# SCH_555-Circuit_2025-03-12.net
KiCad netlist of a schematic drawn in EasyEDA
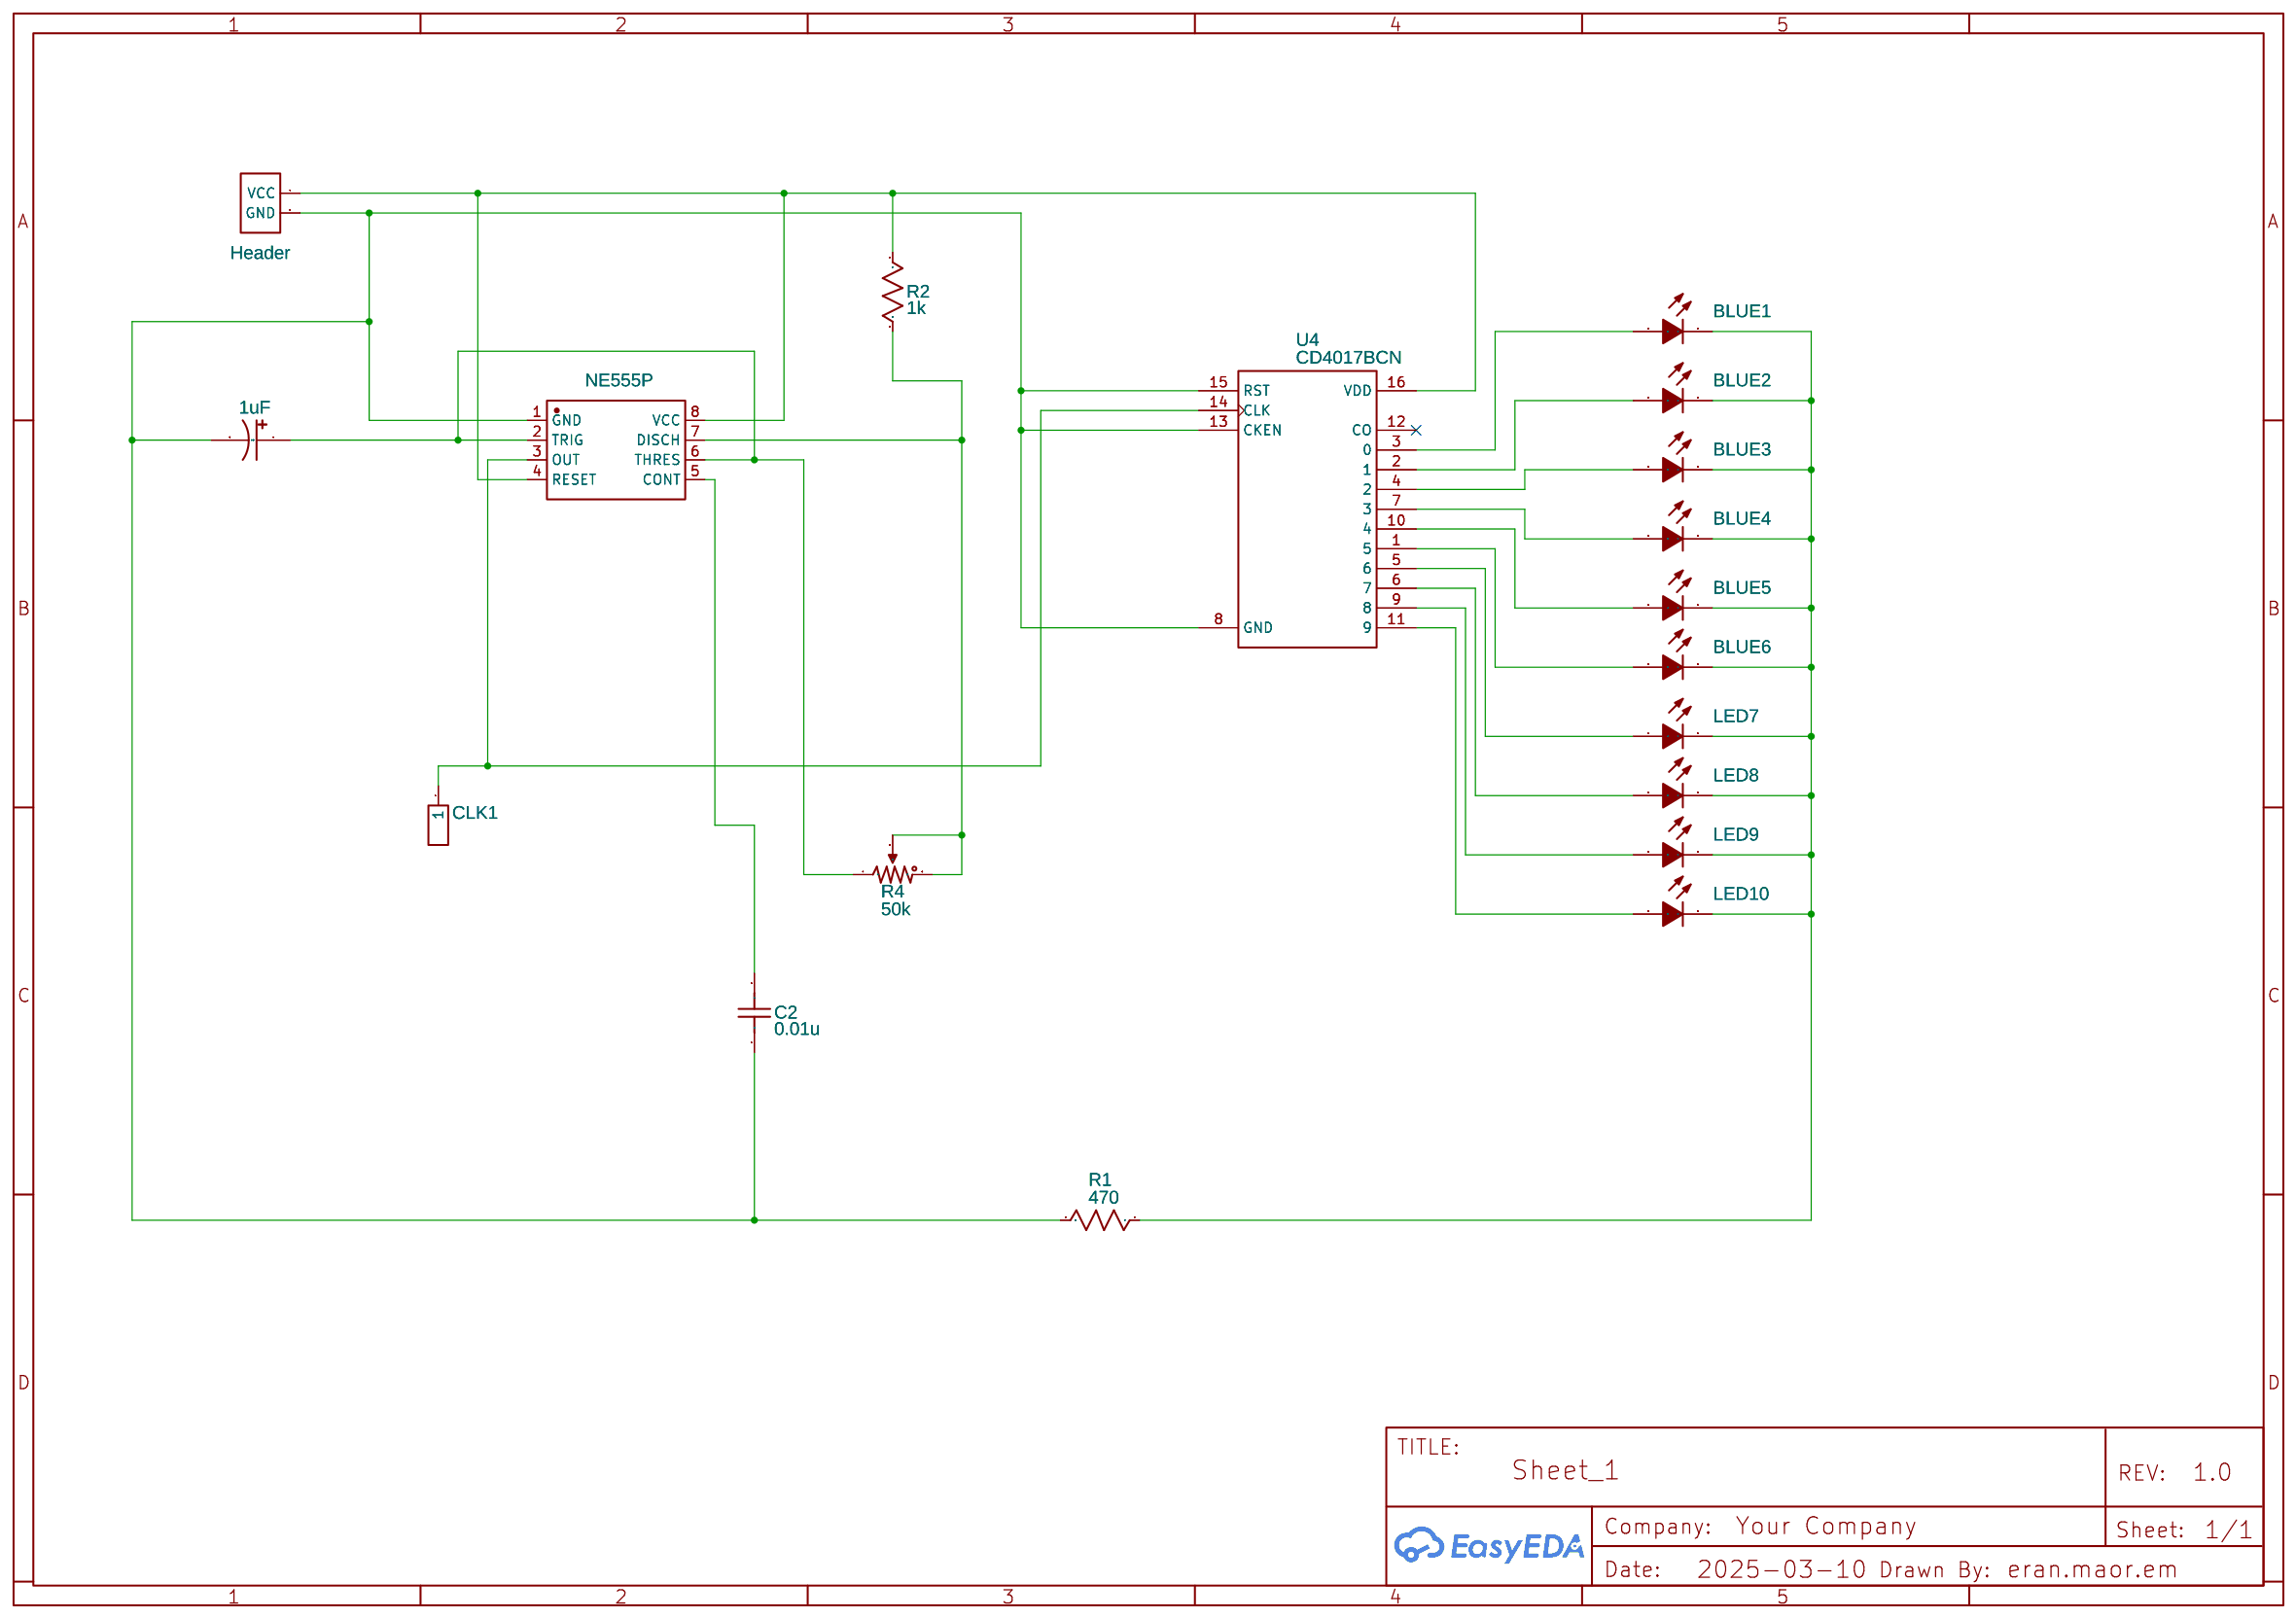
[diagram p0: schematic sheet]

(export (version "E")
  (design (tool "Eeschema 10.0.6"))
  (components
    (comp (ref "BLUE1") (value "LED_5MM") (libsource (lib "") (part "LED_5MM_1")))
    (comp (ref "BLUE2") (value "LED_5MM") (libsource (lib "") (part "LED_5MM_1")))
    (comp (ref "BLUE3") (value "LED_5MM") (libsource (lib "") (part "LED_5MM_1")))
    (comp (ref "BLUE4") (value "LED_5MM") (libsource (lib "") (part "LED_5MM_1")))
    (comp (ref "BLUE5") (value "LED_5MM") (libsource (lib "") (part "LED_5MM_1")))
    (comp (ref "BLUE6") (value "LED_5MM") (libsource (lib "") (part "LED_5MM_1")))
    (comp (ref "C1")
      (value "1uF")
      (fields (field (name "Manufacturer Part") "UVZ1H010MDD") (field (name "Manufacturer") "Nichicon(尼吉康)"))
      (libsource (lib "") (part "UVZ1H010MDD"))
    )
    (comp (ref "C2") (value "0.01u") (libsource (lib "") (part "C_0603_US")))
    (comp (ref "CLK1")
      (value "C81276")
      (fields
        (field (name "Manufacturer Part") "2.54-1*1P针")
        (field (name "Manufacturer") "BOOMELE(Boom Precision Elec)")
      )
      (libsource (lib "") (part "Header-Male-2.54_1x1"))
    )
    (comp (ref "H1") (value "Header") (libsource (lib "") (part "HEADER-FEMALE-2.54_1X2")))
    (comp (ref "LED7") (value "LED_5MM") (libsource (lib "") (part "LED_5MM")))
    (comp (ref "LED8") (value "LED_5MM") (libsource (lib "") (part "LED_5MM")))
    (comp (ref "LED9") (value "LED_5MM") (libsource (lib "") (part "LED_5MM")))
    (comp (ref "LED10") (value "LED_5MM") (libsource (lib "") (part "LED_5MM")))
    (comp (ref "R1")
      (value "470")
      (fields (field (name "Manufacturer Part") "?"))
      (libsource (lib "") (part "Resistor"))
    )
    (comp (ref "R2")
      (value "1k")
      (fields (field (name "Manufacturer Part") "?"))
      (libsource (lib "") (part "Resistor_1"))
    )
    (comp (ref "R4")
      (value "50k")
      (fields (field (name "Manufacturer Part") "?"))
      (libsource (lib "") (part "Potentiometer"))
    )
    (comp (ref "U2")
      (value "NE555P")
      (fields (field (name "Manufacturer") "TI(德州仪器)"))
      (libsource (lib "") (part "NE555P"))
    )
    (comp (ref "U4") (value "CD4017BCN") (libsource (lib "") (part "CD4017BCN")))
  )
  (nets
    (net (code "1") (name "Net-(BLUE1-A)") (class "Default")
      (node (ref "BLUE1") (pin "1") (pinfunction "A_1") (pintype "input"))
      (node (ref "U4") (pin "3") (pinfunction "0_3") (pintype "output"))
    )
    (net (code "2") (name "Net-(BLUE1-K)") (class "Default")
      (node (ref "BLUE1") (pin "2") (pinfunction "K_2") (pintype "input"))
      (node (ref "BLUE2") (pin "2") (pinfunction "K_2") (pintype "input"))
      (node (ref "BLUE3") (pin "2") (pinfunction "K_2") (pintype "input"))
      (node (ref "BLUE4") (pin "2") (pinfunction "K_2") (pintype "input"))
      (node (ref "BLUE5") (pin "2") (pinfunction "K_2") (pintype "input"))
      (node (ref "BLUE6") (pin "2") (pinfunction "K_2") (pintype "input"))
      (node (ref "LED10") (pin "2") (pinfunction "K_2") (pintype "input"))
      (node (ref "LED7") (pin "2") (pinfunction "K_2") (pintype "input"))
      (node (ref "LED8") (pin "2") (pinfunction "K_2") (pintype "input"))
      (node (ref "LED9") (pin "2") (pinfunction "K_2") (pintype "input"))
      (node (ref "R1") (pin "1") (pinfunction "1_1") (pintype "unspecified"))
    )
    (net (code "3") (name "Net-(BLUE2-A)") (class "Default")
      (node (ref "BLUE2") (pin "1") (pinfunction "A_1") (pintype "input"))
      (node (ref "U4") (pin "2") (pinfunction "1_2") (pintype "output"))
    )
    (net (code "4") (name "Net-(BLUE3-A)") (class "Default")
      (node (ref "BLUE3") (pin "1") (pinfunction "A_1") (pintype "input"))
      (node (ref "U4") (pin "4") (pinfunction "2_4") (pintype "output"))
    )
    (net (code "5") (name "Net-(BLUE4-A)") (class "Default")
      (node (ref "BLUE4") (pin "1") (pinfunction "A_1") (pintype "input"))
      (node (ref "U4") (pin "7") (pinfunction "3_7") (pintype "output"))
    )
    (net (code "6") (name "Net-(BLUE5-A)") (class "Default")
      (node (ref "BLUE5") (pin "1") (pinfunction "A_1") (pintype "input"))
      (node (ref "U4") (pin "10") (pinfunction "4_10") (pintype "output"))
    )
    (net (code "7") (name "Net-(BLUE6-A)") (class "Default")
      (node (ref "BLUE6") (pin "1") (pinfunction "A_1") (pintype "input"))
      (node (ref "U4") (pin "1") (pinfunction "5_1") (pintype "output"))
    )
    (net (code "8") (name "Net-(H1-GND)") (class "Default")
      (node (ref "C1") (pin "2") (pinfunction "2_2") (pintype "unspecified"))
      (node (ref "C2") (pin "1") (pinfunction "1_1") (pintype "unspecified"))
      (node (ref "H1") (pin "2") (pinfunction "GND_2") (pintype "unspecified"))
      (node (ref "R1") (pin "2") (pinfunction "2_2") (pintype "unspecified"))
      (node (ref "U2") (pin "1") (pinfunction "GND_1") (pintype "unspecified"))
      (node (ref "U4") (pin "13") (pinfunction "CKEN_13") (pintype "unspecified"))
      (node (ref "U4") (pin "15") (pinfunction "RST_15") (pintype "unspecified"))
      (node (ref "U4") (pin "8") (pinfunction "GND_8") (pintype "passive"))
    )
    (net (code "9") (name "Net-(H1-VCC)") (class "Default")
      (node (ref "H1") (pin "1") (pinfunction "VCC_1") (pintype "unspecified"))
      (node (ref "R2") (pin "1") (pinfunction "1_1") (pintype "unspecified"))
      (node (ref "U2") (pin "4") (pinfunction "RESET_4") (pintype "unspecified"))
      (node (ref "U2") (pin "8") (pinfunction "VCC_8") (pintype "unspecified"))
      (node (ref "U4") (pin "16") (pinfunction "VDD_16") (pintype "passive"))
    )
    (net (code "10") (name "Net-(LED7-A)") (class "Default")
      (node (ref "LED7") (pin "1") (pinfunction "A_1") (pintype "input"))
      (node (ref "U4") (pin "5") (pinfunction "6_5") (pintype "output"))
    )
    (net (code "11") (name "Net-(LED8-A)") (class "Default")
      (node (ref "LED8") (pin "1") (pinfunction "A_1") (pintype "input"))
      (node (ref "U4") (pin "6") (pinfunction "7_6") (pintype "output"))
    )
    (net (code "12") (name "Net-(LED9-A)") (class "Default")
      (node (ref "LED9") (pin "1") (pinfunction "A_1") (pintype "input"))
      (node (ref "U4") (pin "9") (pinfunction "8_9") (pintype "output"))
    )
    (net (code "13") (name "Net-(LED10-A)") (class "Default")
      (node (ref "LED10") (pin "1") (pinfunction "A_1") (pintype "input"))
      (node (ref "U4") (pin "11") (pinfunction "9_11") (pintype "output"))
    )
    (net (code "14") (name "Net-(R4-2)") (class "Default")
      (node (ref "R2") (pin "2") (pinfunction "2_2") (pintype "unspecified"))
      (node (ref "R4") (pin "2") (pinfunction "3_2") (pintype "unspecified"))
      (node (ref "R4") (pin "3") (pinfunction "2_3") (pintype "unspecified"))
      (node (ref "U2") (pin "7") (pinfunction "DISCH_7") (pintype "unspecified"))
    )
    (net (code "15") (name "Net-(U2-CONT)") (class "Default")
      (node (ref "C2") (pin "2") (pinfunction "2_2") (pintype "unspecified"))
      (node (ref "U2") (pin "5") (pinfunction "CONT_5") (pintype "unspecified"))
    )
    (net (code "16") (name "Net-(U2-OUT)") (class "Default")
      (node (ref "CLK1") (pin "1") (pinfunction "1_1") (pintype "unspecified"))
      (node (ref "U2") (pin "3") (pinfunction "OUT_3") (pintype "unspecified"))
      (node (ref "U4") (pin "14") (pinfunction "CLK_14") (pintype "unspecified"))
    )
    (net (code "17") (name "Net-(U2-THRES)") (class "Default")
      (node (ref "C1") (pin "1") (pinfunction "1_1") (pintype "unspecified"))
      (node (ref "R4") (pin "1") (pinfunction "1_1") (pintype "unspecified"))
      (node (ref "U2") (pin "2") (pinfunction "TRIG_2") (pintype "unspecified"))
      (node (ref "U2") (pin "6") (pinfunction "THRES_6") (pintype "unspecified"))
    )
    (net (code "18") (name "unconnected-(U4-CO-Pad12)") (class "Default")
      (node (ref "U4") (pin "12") (pinfunction "CO_12") (pintype "output+no_connect"))
    )
  )
)
